# FAL65816_ram.net
KiCad netlist of a schematic drawn in EAGLE
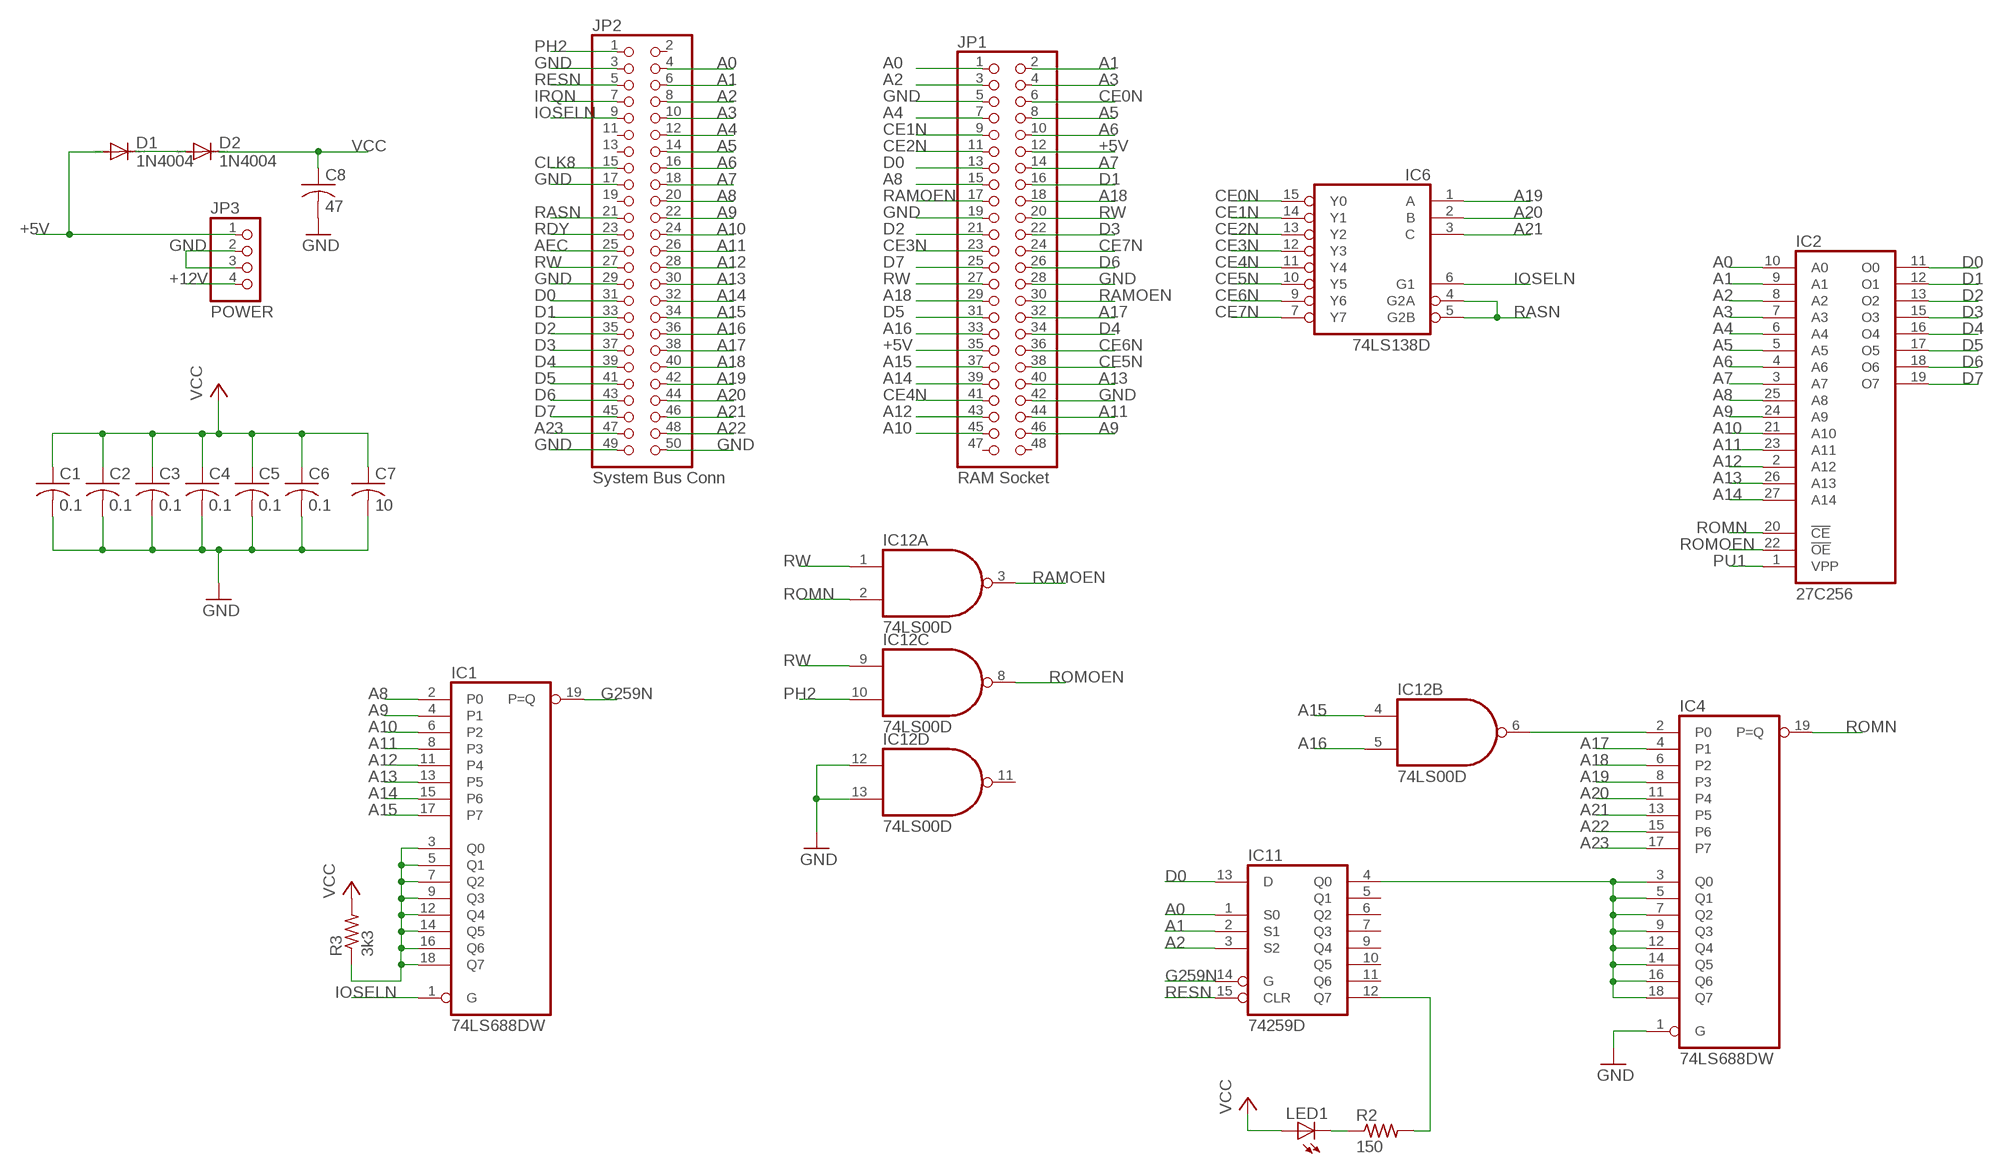
[diagram p0: schematic, sheet 1]

(export (version "E")
  (design (tool "Eeschema 10.0.6"))
  (components
    (comp (ref "C1")
      (value "0.1")
      (footprint "eagle-import:C050-024X044")
      (libsource (lib "eagle-import") (part "C-US050-024X044"))
    )
    (comp (ref "C2")
      (value "0.1")
      (footprint "eagle-import:C050-024X044")
      (libsource (lib "eagle-import") (part "C-US050-024X044"))
    )
    (comp (ref "C3")
      (value "0.1")
      (footprint "eagle-import:C050-024X044")
      (libsource (lib "eagle-import") (part "C-US050-024X044"))
    )
    (comp (ref "C4")
      (value "0.1")
      (footprint "eagle-import:C050-024X044")
      (libsource (lib "eagle-import") (part "C-US050-024X044"))
    )
    (comp (ref "C5")
      (value "0.1")
      (footprint "eagle-import:C050-024X044")
      (libsource (lib "eagle-import") (part "C-US050-024X044"))
    )
    (comp (ref "C6")
      (value "0.1")
      (footprint "eagle-import:C050-024X044")
      (libsource (lib "eagle-import") (part "C-US050-024X044"))
    )
    (comp (ref "C7")
      (value "10")
      (footprint "eagle-import:C050-024X044")
      (libsource (lib "eagle-import") (part "C-US050-024X044"))
    )
    (comp (ref "C8")
      (value "47")
      (footprint "eagle-import:C050-024X044")
      (libsource (lib "eagle-import") (part "C-US050-024X044"))
    )
    (comp (ref "D1")
      (value "1N4004")
      (footprint "eagle-import:DO41-10")
      (libsource (lib "eagle-import") (part "1N4004"))
    )
    (comp (ref "D2")
      (value "1N4004")
      (footprint "eagle-import:DO41-10")
      (libsource (lib "eagle-import") (part "1N4004"))
    )
    (comp (ref "IC1")
      (value "74LS688DW")
      (footprint "eagle-import:SO20W")
      (libsource (lib "eagle-import") (part "74688DWLS"))
    )
    (comp (ref "IC2")
      (value "27C256")
      (footprint "eagle-import:DIL28")
      (libsource (lib "eagle-import") (part "27256"))
    )
    (comp (ref "IC4")
      (value "74LS688DW")
      (footprint "eagle-import:SO20W")
      (libsource (lib "eagle-import") (part "74688DWLS"))
    )
    (comp (ref "IC6")
      (value "74LS138D")
      (footprint "eagle-import:SO16")
      (libsource (lib "eagle-import") (part "74138DLS"))
    )
    (comp (ref "IC11")
      (value "74259D")
      (footprint "eagle-import:SO16")
      (libsource (lib "eagle-import") (part "74259D"))
    )
    (comp (ref "IC12")
      (value "74LS00D")
      (footprint "eagle-import:SO14")
      (libsource (lib "eagle-import") (part "7400DLS"))
    )
    (comp (ref "JP1")
      (value "RAM Socket")
      (footprint "eagle-import:2X24")
      (libsource (lib "eagle-import") (part "PINHD-2X24"))
    )
    (comp (ref "JP2")
      (value "System Bus Conn")
      (footprint "eagle-import:2X25_90")
      (libsource (lib "eagle-import") (part "PINHD-2X25/90"))
    )
    (comp (ref "JP3")
      (value "POWER")
      (footprint "eagle-import:1X04_90")
      (libsource (lib "eagle-import") (part "PINHD-1X4/90"))
    )
    (comp (ref "LED1")
      (value "LED5MM")
      (footprint "eagle-import:LED5MM")
      (libsource (lib "eagle-import") (part "LED5MM"))
    )
    (comp (ref "R2")
      (value "150")
      (footprint "eagle-import:0204_7")
      (libsource (lib "eagle-import") (part "R-US_0204/7"))
    )
    (comp (ref "R3")
      (value "3k3")
      (footprint "eagle-import:0204_7")
      (libsource (lib "eagle-import") (part "R-US_0204/7"))
    )
  )
  (nets
    (net (code "1") (name "/+5V") (class "Default")
      (node (ref "D1") (pin "A") (pinfunction "A_A") (pintype "passive"))
      (node (ref "JP1") (pin "12") (pinfunction "12_12") (pintype "passive"))
      (node (ref "JP1") (pin "35") (pinfunction "35_35") (pintype "passive"))
      (node (ref "JP3") (pin "1") (pinfunction "1_1") (pintype "passive"))
    )
    (net (code "2") (name "/+12V") (class "Default")
      (node (ref "JP3") (pin "4") (pinfunction "4_4") (pintype "passive"))
    )
    (net (code "3") (name "/A0") (class "Default")
      (node (ref "IC11") (pin "1") (pinfunction "S0_1") (pintype "input"))
      (node (ref "IC2") (pin "10") (pinfunction "A0_10") (pintype "input"))
      (node (ref "JP1") (pin "1") (pinfunction "1_1") (pintype "passive"))
      (node (ref "JP2") (pin "4") (pinfunction "4_4") (pintype "passive"))
    )
    (net (code "4") (name "/A1") (class "Default")
      (node (ref "IC11") (pin "2") (pinfunction "S1_2") (pintype "input"))
      (node (ref "IC2") (pin "9") (pinfunction "A1_9") (pintype "input"))
      (node (ref "JP1") (pin "2") (pinfunction "2_2") (pintype "passive"))
      (node (ref "JP2") (pin "6") (pinfunction "6_6") (pintype "passive"))
    )
    (net (code "5") (name "/A2") (class "Default")
      (node (ref "IC11") (pin "3") (pinfunction "S2_3") (pintype "input"))
      (node (ref "IC2") (pin "8") (pinfunction "A2_8") (pintype "input"))
      (node (ref "JP1") (pin "3") (pinfunction "3_3") (pintype "passive"))
      (node (ref "JP2") (pin "8") (pinfunction "8_8") (pintype "passive"))
    )
    (net (code "6") (name "/A3") (class "Default")
      (node (ref "IC2") (pin "7") (pinfunction "A3_7") (pintype "input"))
      (node (ref "JP1") (pin "4") (pinfunction "4_4") (pintype "passive"))
      (node (ref "JP2") (pin "10") (pinfunction "10_10") (pintype "passive"))
    )
    (net (code "7") (name "/A4") (class "Default")
      (node (ref "IC2") (pin "6") (pinfunction "A4_6") (pintype "input"))
      (node (ref "JP1") (pin "7") (pinfunction "7_7") (pintype "passive"))
      (node (ref "JP2") (pin "12") (pinfunction "12_12") (pintype "passive"))
    )
    (net (code "8") (name "/A5") (class "Default")
      (node (ref "IC2") (pin "5") (pinfunction "A5_5") (pintype "input"))
      (node (ref "JP1") (pin "8") (pinfunction "8_8") (pintype "passive"))
      (node (ref "JP2") (pin "14") (pinfunction "14_14") (pintype "passive"))
    )
    (net (code "9") (name "/A6") (class "Default")
      (node (ref "IC2") (pin "4") (pinfunction "A6_4") (pintype "input"))
      (node (ref "JP1") (pin "10") (pinfunction "10_10") (pintype "passive"))
      (node (ref "JP2") (pin "16") (pinfunction "16_16") (pintype "passive"))
    )
    (net (code "10") (name "/A7") (class "Default")
      (node (ref "IC2") (pin "3") (pinfunction "A7_3") (pintype "input"))
      (node (ref "JP1") (pin "14") (pinfunction "14_14") (pintype "passive"))
      (node (ref "JP2") (pin "18") (pinfunction "18_18") (pintype "passive"))
    )
    (net (code "11") (name "/A8") (class "Default")
      (node (ref "IC1") (pin "2") (pinfunction "P0_2") (pintype "input"))
      (node (ref "IC2") (pin "25") (pinfunction "A8_25") (pintype "input"))
      (node (ref "JP1") (pin "15") (pinfunction "15_15") (pintype "passive"))
      (node (ref "JP2") (pin "20") (pinfunction "20_20") (pintype "passive"))
    )
    (net (code "12") (name "/A9") (class "Default")
      (node (ref "IC1") (pin "4") (pinfunction "P1_4") (pintype "input"))
      (node (ref "IC2") (pin "24") (pinfunction "A9_24") (pintype "input"))
      (node (ref "JP1") (pin "46") (pinfunction "46_46") (pintype "passive"))
      (node (ref "JP2") (pin "22") (pinfunction "22_22") (pintype "passive"))
    )
    (net (code "13") (name "/A10") (class "Default")
      (node (ref "IC1") (pin "6") (pinfunction "P2_6") (pintype "input"))
      (node (ref "IC2") (pin "21") (pinfunction "A10_21") (pintype "input"))
      (node (ref "JP1") (pin "45") (pinfunction "45_45") (pintype "passive"))
      (node (ref "JP2") (pin "24") (pinfunction "24_24") (pintype "passive"))
    )
    (net (code "14") (name "/A11") (class "Default")
      (node (ref "IC1") (pin "8") (pinfunction "P3_8") (pintype "input"))
      (node (ref "IC2") (pin "23") (pinfunction "A11_23") (pintype "input"))
      (node (ref "JP1") (pin "44") (pinfunction "44_44") (pintype "passive"))
      (node (ref "JP2") (pin "26") (pinfunction "26_26") (pintype "passive"))
    )
    (net (code "15") (name "/A12") (class "Default")
      (node (ref "IC1") (pin "11") (pinfunction "P4_11") (pintype "input"))
      (node (ref "IC2") (pin "2") (pinfunction "A12_2") (pintype "input"))
      (node (ref "JP1") (pin "43") (pinfunction "43_43") (pintype "passive"))
      (node (ref "JP2") (pin "28") (pinfunction "28_28") (pintype "passive"))
    )
    (net (code "16") (name "/A13") (class "Default")
      (node (ref "IC1") (pin "13") (pinfunction "P5_13") (pintype "input"))
      (node (ref "IC2") (pin "26") (pinfunction "A13_26") (pintype "input"))
      (node (ref "JP1") (pin "40") (pinfunction "40_40") (pintype "passive"))
      (node (ref "JP2") (pin "30") (pinfunction "30_30") (pintype "passive"))
    )
    (net (code "17") (name "/A14") (class "Default")
      (node (ref "IC1") (pin "15") (pinfunction "P6_15") (pintype "input"))
      (node (ref "IC2") (pin "27") (pinfunction "A14_27") (pintype "input"))
      (node (ref "JP1") (pin "39") (pinfunction "39_39") (pintype "passive"))
      (node (ref "JP2") (pin "32") (pinfunction "32_32") (pintype "passive"))
    )
    (net (code "18") (name "/A15") (class "Default")
      (node (ref "IC1") (pin "17") (pinfunction "P7_17") (pintype "input"))
      (node (ref "IC12") (pin "4") (pinfunction "I0_4") (pintype "input"))
      (node (ref "JP1") (pin "37") (pinfunction "37_37") (pintype "passive"))
      (node (ref "JP2") (pin "34") (pinfunction "34_34") (pintype "passive"))
    )
    (net (code "19") (name "/A16") (class "Default")
      (node (ref "IC12") (pin "5") (pinfunction "I1_5") (pintype "input"))
      (node (ref "JP1") (pin "33") (pinfunction "33_33") (pintype "passive"))
      (node (ref "JP2") (pin "36") (pinfunction "36_36") (pintype "passive"))
    )
    (net (code "20") (name "/A17") (class "Default")
      (node (ref "IC4") (pin "4") (pinfunction "P1_4") (pintype "input"))
      (node (ref "JP1") (pin "32") (pinfunction "32_32") (pintype "passive"))
      (node (ref "JP2") (pin "38") (pinfunction "38_38") (pintype "passive"))
    )
    (net (code "21") (name "/A18") (class "Default")
      (node (ref "IC4") (pin "6") (pinfunction "P2_6") (pintype "input"))
      (node (ref "JP1") (pin "18") (pinfunction "18_18") (pintype "passive"))
      (node (ref "JP1") (pin "29") (pinfunction "29_29") (pintype "passive"))
      (node (ref "JP2") (pin "40") (pinfunction "40_40") (pintype "passive"))
    )
    (net (code "22") (name "/A19") (class "Default")
      (node (ref "IC4") (pin "8") (pinfunction "P3_8") (pintype "input"))
      (node (ref "IC6") (pin "1") (pinfunction "A_1") (pintype "input"))
      (node (ref "JP2") (pin "42") (pinfunction "42_42") (pintype "passive"))
    )
    (net (code "23") (name "/A20") (class "Default")
      (node (ref "IC4") (pin "11") (pinfunction "P4_11") (pintype "input"))
      (node (ref "IC6") (pin "2") (pinfunction "B_2") (pintype "input"))
      (node (ref "JP2") (pin "44") (pinfunction "44_44") (pintype "passive"))
    )
    (net (code "24") (name "/A21") (class "Default")
      (node (ref "IC4") (pin "13") (pinfunction "P5_13") (pintype "input"))
      (node (ref "IC6") (pin "3") (pinfunction "C_3") (pintype "input"))
      (node (ref "JP2") (pin "46") (pinfunction "46_46") (pintype "passive"))
    )
    (net (code "25") (name "/A22") (class "Default")
      (node (ref "IC4") (pin "15") (pinfunction "P6_15") (pintype "input"))
      (node (ref "JP2") (pin "48") (pinfunction "48_48") (pintype "passive"))
    )
    (net (code "26") (name "/A23") (class "Default")
      (node (ref "IC4") (pin "17") (pinfunction "P7_17") (pintype "input"))
      (node (ref "JP2") (pin "47") (pinfunction "47_47") (pintype "passive"))
    )
    (net (code "27") (name "/AEC") (class "Default")
      (node (ref "JP2") (pin "25") (pinfunction "25_25") (pintype "passive"))
    )
    (net (code "28") (name "/CE0N") (class "Default")
      (node (ref "IC6") (pin "15") (pinfunction "Y0_15") (pintype "output"))
      (node (ref "JP1") (pin "6") (pinfunction "6_6") (pintype "passive"))
    )
    (net (code "29") (name "/CE1N") (class "Default")
      (node (ref "IC6") (pin "14") (pinfunction "Y1_14") (pintype "output"))
      (node (ref "JP1") (pin "9") (pinfunction "9_9") (pintype "passive"))
    )
    (net (code "30") (name "/CE2N") (class "Default")
      (node (ref "IC6") (pin "13") (pinfunction "Y2_13") (pintype "output"))
      (node (ref "JP1") (pin "11") (pinfunction "11_11") (pintype "passive"))
    )
    (net (code "31") (name "/CE3N") (class "Default")
      (node (ref "IC6") (pin "12") (pinfunction "Y3_12") (pintype "output"))
      (node (ref "JP1") (pin "23") (pinfunction "23_23") (pintype "passive"))
    )
    (net (code "32") (name "/CE4N") (class "Default")
      (node (ref "IC6") (pin "11") (pinfunction "Y4_11") (pintype "output"))
      (node (ref "JP1") (pin "41") (pinfunction "41_41") (pintype "passive"))
    )
    (net (code "33") (name "/CE5N") (class "Default")
      (node (ref "IC6") (pin "10") (pinfunction "Y5_10") (pintype "output"))
      (node (ref "JP1") (pin "38") (pinfunction "38_38") (pintype "passive"))
    )
    (net (code "34") (name "/CE6N") (class "Default")
      (node (ref "IC6") (pin "9") (pinfunction "Y6_9") (pintype "output"))
      (node (ref "JP1") (pin "36") (pinfunction "36_36") (pintype "passive"))
    )
    (net (code "35") (name "/CE7N") (class "Default")
      (node (ref "IC6") (pin "7") (pinfunction "Y7_7") (pintype "output"))
      (node (ref "JP1") (pin "24") (pinfunction "24_24") (pintype "passive"))
    )
    (net (code "36") (name "/CLK8") (class "Default")
      (node (ref "JP2") (pin "15") (pinfunction "15_15") (pintype "passive"))
    )
    (net (code "37") (name "/D0") (class "Default")
      (node (ref "IC11") (pin "13") (pinfunction "D_13") (pintype "input"))
      (node (ref "IC2") (pin "11") (pinfunction "O0_11") (pintype "tri_state"))
      (node (ref "JP1") (pin "13") (pinfunction "13_13") (pintype "passive"))
      (node (ref "JP2") (pin "31") (pinfunction "31_31") (pintype "passive"))
    )
    (net (code "38") (name "/D1") (class "Default")
      (node (ref "IC2") (pin "12") (pinfunction "O1_12") (pintype "tri_state"))
      (node (ref "JP1") (pin "16") (pinfunction "16_16") (pintype "passive"))
      (node (ref "JP2") (pin "33") (pinfunction "33_33") (pintype "passive"))
    )
    (net (code "39") (name "/D2") (class "Default")
      (node (ref "IC2") (pin "13") (pinfunction "O2_13") (pintype "tri_state"))
      (node (ref "JP1") (pin "21") (pinfunction "21_21") (pintype "passive"))
      (node (ref "JP2") (pin "35") (pinfunction "35_35") (pintype "passive"))
    )
    (net (code "40") (name "/D3") (class "Default")
      (node (ref "IC2") (pin "15") (pinfunction "O3_15") (pintype "tri_state"))
      (node (ref "JP1") (pin "22") (pinfunction "22_22") (pintype "passive"))
      (node (ref "JP2") (pin "37") (pinfunction "37_37") (pintype "passive"))
    )
    (net (code "41") (name "/D4") (class "Default")
      (node (ref "IC2") (pin "16") (pinfunction "O4_16") (pintype "tri_state"))
      (node (ref "JP1") (pin "34") (pinfunction "34_34") (pintype "passive"))
      (node (ref "JP2") (pin "39") (pinfunction "39_39") (pintype "passive"))
    )
    (net (code "42") (name "/D5") (class "Default")
      (node (ref "IC2") (pin "17") (pinfunction "O5_17") (pintype "tri_state"))
      (node (ref "JP1") (pin "31") (pinfunction "31_31") (pintype "passive"))
      (node (ref "JP2") (pin "41") (pinfunction "41_41") (pintype "passive"))
    )
    (net (code "43") (name "/D6") (class "Default")
      (node (ref "IC2") (pin "18") (pinfunction "O6_18") (pintype "tri_state"))
      (node (ref "JP1") (pin "26") (pinfunction "26_26") (pintype "passive"))
      (node (ref "JP2") (pin "43") (pinfunction "43_43") (pintype "passive"))
    )
    (net (code "44") (name "/D7") (class "Default")
      (node (ref "IC2") (pin "19") (pinfunction "O7_19") (pintype "tri_state"))
      (node (ref "JP1") (pin "25") (pinfunction "25_25") (pintype "passive"))
      (node (ref "JP2") (pin "45") (pinfunction "45_45") (pintype "passive"))
    )
    (net (code "45") (name "/G259N") (class "Default")
      (node (ref "IC1") (pin "19") (pinfunction "P=Q_19") (pintype "output"))
      (node (ref "IC11") (pin "14") (pinfunction "G_14") (pintype "input"))
    )
    (net (code "46") (name "/IOSELN") (class "Default")
      (node (ref "IC1") (pin "1") (pinfunction "G_1") (pintype "input"))
      (node (ref "IC6") (pin "6") (pinfunction "G1_6") (pintype "input"))
      (node (ref "JP2") (pin "9") (pinfunction "9_9") (pintype "passive"))
    )
    (net (code "47") (name "/IRQN") (class "Default")
      (node (ref "JP2") (pin "7") (pinfunction "7_7") (pintype "passive"))
    )
    (net (code "48") (name "/PH2") (class "Default")
      (node (ref "IC12") (pin "10") (pinfunction "I1_10") (pintype "input"))
      (node (ref "JP2") (pin "1") (pinfunction "1_1") (pintype "passive"))
    )
    (net (code "49") (name "/PU1") (class "Default")
      (node (ref "IC1") (pin "12") (pinfunction "Q4_12") (pintype "input"))
      (node (ref "IC1") (pin "14") (pinfunction "Q5_14") (pintype "input"))
      (node (ref "IC1") (pin "16") (pinfunction "Q6_16") (pintype "input"))
      (node (ref "IC1") (pin "18") (pinfunction "Q7_18") (pintype "input"))
      (node (ref "IC1") (pin "3") (pinfunction "Q0_3") (pintype "input"))
      (node (ref "IC1") (pin "5") (pinfunction "Q1_5") (pintype "input"))
      (node (ref "IC1") (pin "7") (pinfunction "Q2_7") (pintype "input"))
      (node (ref "IC1") (pin "9") (pinfunction "Q3_9") (pintype "input"))
      (node (ref "IC2") (pin "1") (pinfunction "VPP_1") (pintype "input"))
      (node (ref "R3") (pin "1") (pinfunction "1_1") (pintype "passive"))
    )
    (net (code "50") (name "/RAMOEN") (class "Default")
      (node (ref "IC12") (pin "3") (pinfunction "O_3") (pintype "output"))
      (node (ref "JP1") (pin "17") (pinfunction "17_17") (pintype "passive"))
      (node (ref "JP1") (pin "30") (pinfunction "30_30") (pintype "passive"))
    )
    (net (code "51") (name "/RASN") (class "Default")
      (node (ref "IC6") (pin "4") (pinfunction "G2A_4") (pintype "input"))
      (node (ref "IC6") (pin "5") (pinfunction "G2B_5") (pintype "input"))
      (node (ref "JP2") (pin "21") (pinfunction "21_21") (pintype "passive"))
    )
    (net (code "52") (name "/RDY") (class "Default")
      (node (ref "JP2") (pin "23") (pinfunction "23_23") (pintype "passive"))
    )
    (net (code "53") (name "/RESN") (class "Default")
      (node (ref "IC11") (pin "15") (pinfunction "CLR_15") (pintype "input"))
      (node (ref "JP2") (pin "5") (pinfunction "5_5") (pintype "passive"))
    )
    (net (code "54") (name "/ROMN") (class "Default")
      (node (ref "IC12") (pin "2") (pinfunction "I1_2") (pintype "input"))
      (node (ref "IC2") (pin "20") (pinfunction "~{CE}_20") (pintype "input"))
      (node (ref "IC4") (pin "19") (pinfunction "P=Q_19") (pintype "output"))
    )
    (net (code "55") (name "/ROMOEN") (class "Default")
      (node (ref "IC12") (pin "8") (pinfunction "O_8") (pintype "output"))
      (node (ref "IC2") (pin "22") (pinfunction "~{OE}_22") (pintype "input"))
    )
    (net (code "56") (name "/RW") (class "Default")
      (node (ref "IC12") (pin "1") (pinfunction "I0_1") (pintype "input"))
      (node (ref "IC12") (pin "9") (pinfunction "I0_9") (pintype "input"))
      (node (ref "JP1") (pin "20") (pinfunction "20_20") (pintype "passive"))
      (node (ref "JP1") (pin "27") (pinfunction "27_27") (pintype "passive"))
      (node (ref "JP2") (pin "27") (pinfunction "27_27") (pintype "passive"))
    )
    (net (code "57") (name "GND") (class "Default")
      (node (ref "C1") (pin "2") (pinfunction "2_2") (pintype "passive"))
      (node (ref "C2") (pin "2") (pinfunction "2_2") (pintype "passive"))
      (node (ref "C3") (pin "2") (pinfunction "2_2") (pintype "passive"))
      (node (ref "C4") (pin "2") (pinfunction "2_2") (pintype "passive"))
      (node (ref "C5") (pin "2") (pinfunction "2_2") (pintype "passive"))
      (node (ref "C6") (pin "2") (pinfunction "2_2") (pintype "passive"))
      (node (ref "C7") (pin "2") (pinfunction "2_2") (pintype "passive"))
      (node (ref "C8") (pin "2") (pinfunction "2_2") (pintype "passive"))
      (node (ref "IC12") (pin "12") (pinfunction "I0_12") (pintype "input"))
      (node (ref "IC12") (pin "13") (pinfunction "I1_13") (pintype "input"))
      (node (ref "IC4") (pin "1") (pinfunction "G_1") (pintype "input"))
      (node (ref "JP1") (pin "19") (pinfunction "19_19") (pintype "passive"))
      (node (ref "JP1") (pin "28") (pinfunction "28_28") (pintype "passive"))
      (node (ref "JP1") (pin "42") (pinfunction "42_42") (pintype "passive"))
      (node (ref "JP1") (pin "5") (pinfunction "5_5") (pintype "passive"))
      (node (ref "JP2") (pin "17") (pinfunction "17_17") (pintype "passive"))
      (node (ref "JP2") (pin "29") (pinfunction "29_29") (pintype "passive"))
      (node (ref "JP2") (pin "3") (pinfunction "3_3") (pintype "passive"))
      (node (ref "JP2") (pin "49") (pinfunction "49_49") (pintype "passive"))
      (node (ref "JP2") (pin "50") (pinfunction "50_50") (pintype "passive"))
      (node (ref "JP3") (pin "2") (pinfunction "2_2") (pintype "passive"))
      (node (ref "JP3") (pin "3") (pinfunction "3_3") (pintype "passive"))
    )
    (net (code "58") (name "Net-(D1-PadC)") (class "Default")
      (node (ref "D1") (pin "C") (pinfunction "C_C") (pintype "passive"))
      (node (ref "D2") (pin "A") (pinfunction "A_A") (pintype "passive"))
    )
    (net (code "59") (name "Net-(IC11A-Q0)") (class "Default")
      (node (ref "IC11") (pin "4") (pinfunction "Q0_4") (pintype "output"))
      (node (ref "IC4") (pin "12") (pinfunction "Q4_12") (pintype "input"))
      (node (ref "IC4") (pin "14") (pinfunction "Q5_14") (pintype "input"))
      (node (ref "IC4") (pin "16") (pinfunction "Q6_16") (pintype "input"))
      (node (ref "IC4") (pin "18") (pinfunction "Q7_18") (pintype "input"))
      (node (ref "IC4") (pin "3") (pinfunction "Q0_3") (pintype "input"))
      (node (ref "IC4") (pin "5") (pinfunction "Q1_5") (pintype "input"))
      (node (ref "IC4") (pin "7") (pinfunction "Q2_7") (pintype "input"))
      (node (ref "IC4") (pin "9") (pinfunction "Q3_9") (pintype "input"))
    )
    (net (code "60") (name "Net-(IC11A-Q7)") (class "Default")
      (node (ref "IC11") (pin "12") (pinfunction "Q7_12") (pintype "output"))
      (node (ref "R2") (pin "2") (pinfunction "2_2") (pintype "passive"))
    )
    (net (code "61") (name "Net-(IC12B-O)") (class "Default")
      (node (ref "IC12") (pin "6") (pinfunction "O_6") (pintype "output"))
      (node (ref "IC4") (pin "2") (pinfunction "P0_2") (pintype "input"))
    )
    (net (code "62") (name "Net-(LED1-C)") (class "Default")
      (node (ref "LED1") (pin "K") (pinfunction "C_K") (pintype "passive"))
      (node (ref "R2") (pin "1") (pinfunction "1_1") (pintype "passive"))
    )
    (net (code "63") (name "VCC") (class "Default")
      (node (ref "C1") (pin "1") (pinfunction "1_1") (pintype "passive"))
      (node (ref "C2") (pin "1") (pinfunction "1_1") (pintype "passive"))
      (node (ref "C3") (pin "1") (pinfunction "1_1") (pintype "passive"))
      (node (ref "C4") (pin "1") (pinfunction "1_1") (pintype "passive"))
      (node (ref "C5") (pin "1") (pinfunction "1_1") (pintype "passive"))
      (node (ref "C6") (pin "1") (pinfunction "1_1") (pintype "passive"))
      (node (ref "C7") (pin "1") (pinfunction "1_1") (pintype "passive"))
      (node (ref "C8") (pin "1") (pinfunction "1_1") (pintype "passive"))
      (node (ref "D2") (pin "C") (pinfunction "C_C") (pintype "passive"))
      (node (ref "LED1") (pin "A") (pinfunction "A_A") (pintype "passive"))
      (node (ref "R3") (pin "2") (pinfunction "2_2") (pintype "passive"))
    )
    (net (code "64") (name "unconnected-(IC11A-Q1-Pad5)") (class "Default")
      (node (ref "IC11") (pin "5") (pinfunction "Q1_5") (pintype "output"))
    )
    (net (code "65") (name "unconnected-(IC11A-Q2-Pad6)") (class "Default")
      (node (ref "IC11") (pin "6") (pinfunction "Q2_6") (pintype "output"))
    )
    (net (code "66") (name "unconnected-(IC11A-Q3-Pad7)") (class "Default")
      (node (ref "IC11") (pin "7") (pinfunction "Q3_7") (pintype "output"))
    )
    (net (code "67") (name "unconnected-(IC11A-Q4-Pad9)") (class "Default")
      (node (ref "IC11") (pin "9") (pinfunction "Q4_9") (pintype "output"))
    )
    (net (code "68") (name "unconnected-(IC11A-Q5-Pad10)") (class "Default")
      (node (ref "IC11") (pin "10") (pinfunction "Q5_10") (pintype "output"))
    )
    (net (code "69") (name "unconnected-(IC11A-Q6-Pad11)") (class "Default")
      (node (ref "IC11") (pin "11") (pinfunction "Q6_11") (pintype "output"))
    )
    (net (code "70") (name "unconnected-(IC12D-O-Pad11)") (class "Default")
      (node (ref "IC12") (pin "11") (pinfunction "O_11") (pintype "output"))
    )
    (net (code "71") (name "unconnected-(JP1-Pad47)") (class "Default")
      (node (ref "JP1") (pin "47") (pinfunction "47_47") (pintype "passive"))
    )
    (net (code "72") (name "unconnected-(JP1-Pad48)") (class "Default")
      (node (ref "JP1") (pin "48") (pinfunction "48_48") (pintype "passive"))
    )
    (net (code "73") (name "unconnected-(JP2-Pad2)") (class "Default")
      (node (ref "JP2") (pin "2") (pinfunction "2_2") (pintype "passive"))
    )
    (net (code "74") (name "unconnected-(JP2-Pad11)") (class "Default")
      (node (ref "JP2") (pin "11") (pinfunction "11_11") (pintype "passive"))
    )
    (net (code "75") (name "unconnected-(JP2-Pad13)") (class "Default")
      (node (ref "JP2") (pin "13") (pinfunction "13_13") (pintype "passive"))
    )
    (net (code "76") (name "unconnected-(JP2-Pad19)") (class "Default")
      (node (ref "JP2") (pin "19") (pinfunction "19_19") (pintype "passive"))
    )
  )
)
